# bmsMaster_conn.net
KiCad netlist of a schematic drawn in Altium Designer
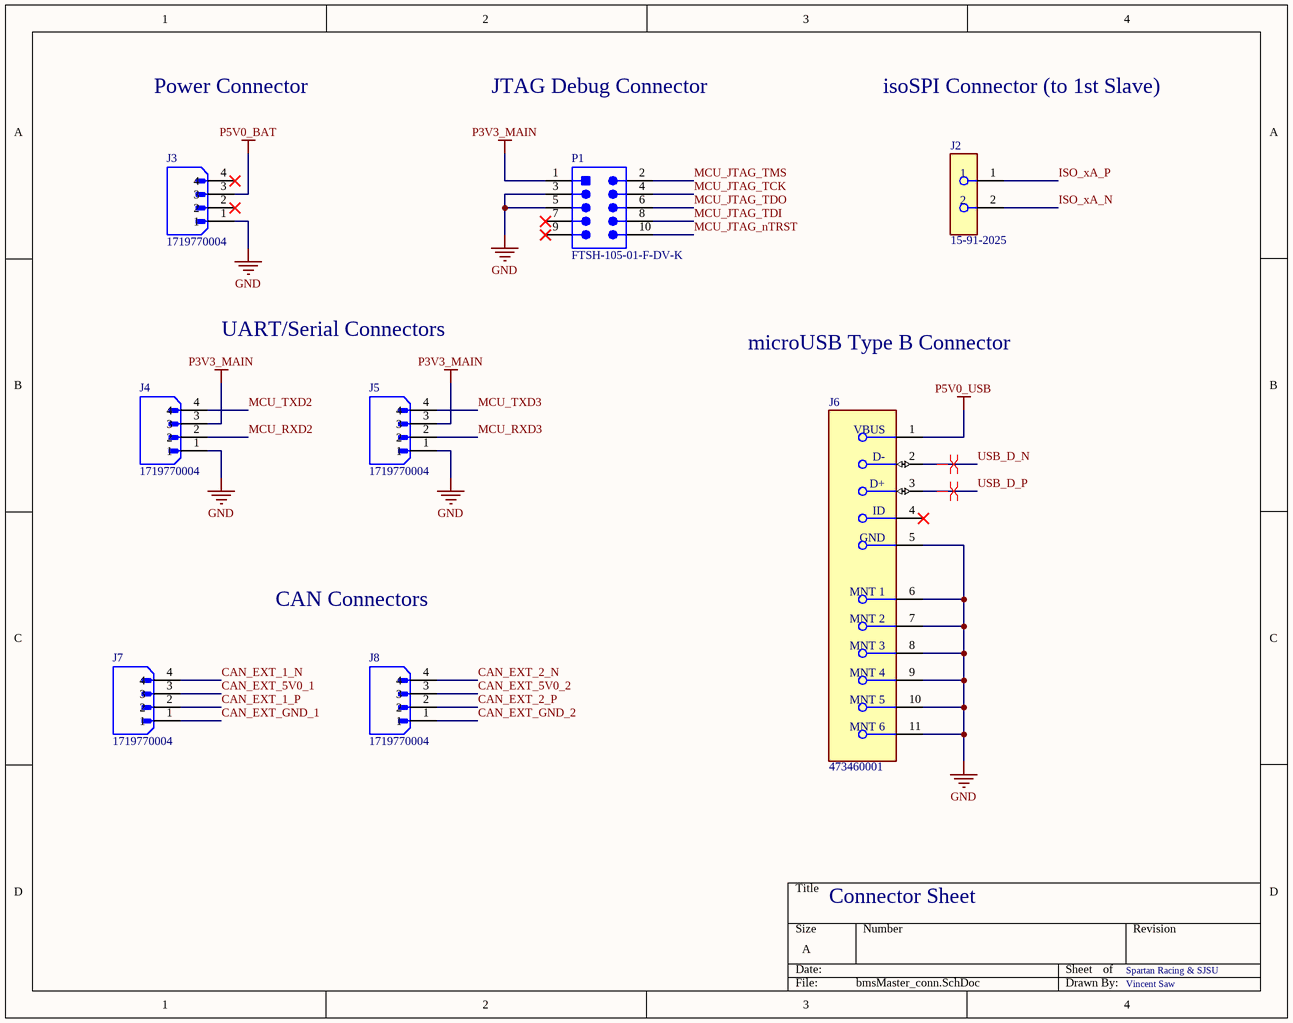
[diagram p0: bmsMaster_conn.SchDoc]

(export (version "E")
  (design (tool "Eeschema 10.0.6"))
  (components
    (comp (ref "J2")
      (value "15-91-2025")
      (footprint "FP-15-91-2025-MFG")
      (description "CONN HEADER SMD R/A 2POS 2.54MM")
      (libsource (lib "Altium Content Vault") (part "3ddab50f66188bb7952c54a1b76274c"))
    )
    (comp (ref "J3")
      (value "1719770004")
      (footprint "171977-0004:MOLEX_1719770004")
      (fields (field (name "MF") "{'manufacturer': u'Molex'}"))
      (libsource (lib "*") (part "1719770004"))
    )
    (comp (ref "J4")
      (value "1719770004")
      (footprint "171977-0004:MOLEX_1719770004")
      (fields (field (name "MF") "{'manufacturer': u'Molex'}"))
      (libsource (lib "*") (part "1719770004"))
    )
    (comp (ref "J5")
      (value "1719770004")
      (footprint "171977-0004:MOLEX_1719770004")
      (fields (field (name "MF") "{'manufacturer': u'Molex'}"))
      (libsource (lib "*") (part "1719770004"))
    )
    (comp (ref "J6")
      (value "473460001")
      (footprint "FP-473460001-MFG")
      (description "CONN RCPT USB2.0 MICRO B SMD R/A")
      (fields
        (field (name "OCTOPART") "https://octopart.com/47346-0001-molex-7164928")
        (field (name "MANUFACTURER") "Molex")
      )
      (libsource (lib "Altium Content Vault") (part "53ae1f1d9b557310b43ca686e5bb76a"))
    )
    (comp (ref "J7")
      (value "1719770004")
      (footprint "171977-0004:MOLEX_1719770004")
      (fields (field (name "MF") "{'manufacturer': u'Molex'}"))
      (libsource (lib "*") (part "1719770004"))
    )
    (comp (ref "J8")
      (value "1719770004")
      (footprint "171977-0004:MOLEX_1719770004")
      (fields (field (name "MF") "{'manufacturer': u'Molex'}"))
      (libsource (lib "*") (part "1719770004"))
    )
    (comp (ref "P1")
      (value "FTSH-105-01-F-DV-K")
      (footprint "SMTC-FTSH-105-01-L-DV-K_V")
      (description "Male Header, Pitch 1.27 mm, 2 x 5 Position, Height 6.12 mm, RoHS, Tube")
      (fields (field (name "MANUFACTURER") "Samtec"))
      (libsource (lib "Altium Content Vault") (part "CN-2P-M-R10"))
    )
  )
  (nets
    (net (code "1") (name "/CAN_EXT_1_N") (class "Default")
      (node (ref "J7") (pin "4") (pinfunction "4_4") (pintype "passive"))
    )
    (net (code "2") (name "/CAN_EXT_1_P") (class "Default")
      (node (ref "J7") (pin "2") (pinfunction "2_2") (pintype "passive"))
    )
    (net (code "3") (name "/CAN_EXT_2_N") (class "Default")
      (node (ref "J8") (pin "4") (pinfunction "4_4") (pintype "passive"))
    )
    (net (code "4") (name "/CAN_EXT_2_P") (class "Default")
      (node (ref "J8") (pin "2") (pinfunction "2_2") (pintype "passive"))
    )
    (net (code "5") (name "/CAN_EXT_5V0_1") (class "Default")
      (node (ref "J7") (pin "3") (pinfunction "3_3") (pintype "passive"))
    )
    (net (code "6") (name "/CAN_EXT_5V0_2") (class "Default")
      (node (ref "J8") (pin "3") (pinfunction "3_3") (pintype "passive"))
    )
    (net (code "7") (name "/CAN_EXT_GND_1") (class "Default")
      (node (ref "J7") (pin "1") (pinfunction "1_1") (pintype "passive"))
    )
    (net (code "8") (name "/CAN_EXT_GND_2") (class "Default")
      (node (ref "J8") (pin "1") (pinfunction "1_1") (pintype "passive"))
    )
    (net (code "9") (name "/ISO_xA_N") (class "Default")
      (node (ref "J2") (pin "2") (pinfunction "2_2") (pintype "passive"))
    )
    (net (code "10") (name "/ISO_xA_P") (class "Default")
      (node (ref "J2") (pin "1") (pinfunction "1_1") (pintype "passive"))
    )
    (net (code "11") (name "/MCU_JTAG_TCK") (class "Default")
      (node (ref "P1") (pin "4") (pinfunction "4_4") (pintype "passive"))
    )
    (net (code "12") (name "/MCU_JTAG_TDI") (class "Default")
      (node (ref "P1") (pin "8") (pinfunction "8_8") (pintype "passive"))
    )
    (net (code "13") (name "/MCU_JTAG_TDO") (class "Default")
      (node (ref "P1") (pin "6") (pinfunction "6_6") (pintype "passive"))
    )
    (net (code "14") (name "/MCU_JTAG_TMS") (class "Default")
      (node (ref "P1") (pin "2") (pinfunction "2_2") (pintype "passive"))
    )
    (net (code "15") (name "/MCU_JTAG_nTRST") (class "Default")
      (node (ref "P1") (pin "10") (pinfunction "10_10") (pintype "passive"))
    )
    (net (code "16") (name "/MCU_RXD2") (class "Default")
      (node (ref "J4") (pin "2") (pinfunction "2_2") (pintype "passive"))
    )
    (net (code "17") (name "/MCU_RXD3") (class "Default")
      (node (ref "J5") (pin "2") (pinfunction "2_2") (pintype "passive"))
    )
    (net (code "18") (name "/MCU_TXD2") (class "Default")
      (node (ref "J4") (pin "4") (pinfunction "4_4") (pintype "passive"))
    )
    (net (code "19") (name "/MCU_TXD3") (class "Default")
      (node (ref "J5") (pin "4") (pinfunction "4_4") (pintype "passive"))
    )
    (net (code "20") (name "/USB_D_N") (class "Default")
      (node (ref "J6") (pin "2") (pinfunction "D-_2") (pintype "bidirectional"))
    )
    (net (code "21") (name "/USB_D_P") (class "Default")
      (node (ref "J6") (pin "3") (pinfunction "D+_3") (pintype "bidirectional"))
    )
    (net (code "22") (name "GND") (class "Default")
      (node (ref "J3") (pin "1") (pinfunction "1_1") (pintype "passive"))
      (node (ref "J4") (pin "1") (pinfunction "1_1") (pintype "passive"))
      (node (ref "J5") (pin "1") (pinfunction "1_1") (pintype "passive"))
      (node (ref "J6") (pin "10") (pinfunction "MNT_5_10") (pintype "passive"))
      (node (ref "J6") (pin "11") (pinfunction "MNT_6_11") (pintype "passive"))
      (node (ref "J6") (pin "5") (pinfunction "GND_5") (pintype "power_in"))
      (node (ref "J6") (pin "6") (pinfunction "MNT_1_6") (pintype "passive"))
      (node (ref "J6") (pin "7") (pinfunction "MNT_2_7") (pintype "passive"))
      (node (ref "J6") (pin "8") (pinfunction "MNT_3_8") (pintype "passive"))
      (node (ref "J6") (pin "9") (pinfunction "MNT_4_9") (pintype "passive"))
      (node (ref "P1") (pin "3") (pinfunction "3_3") (pintype "passive"))
      (node (ref "P1") (pin "5") (pinfunction "5_5") (pintype "passive"))
    )
    (net (code "23") (name "P3V3_MAIN") (class "Default")
      (node (ref "J4") (pin "3") (pinfunction "3_3") (pintype "passive"))
      (node (ref "J5") (pin "3") (pinfunction "3_3") (pintype "passive"))
      (node (ref "P1") (pin "1") (pinfunction "1_1") (pintype "passive"))
    )
    (net (code "24") (name "P5V0_BAT") (class "Default")
      (node (ref "J3") (pin "3") (pinfunction "3_3") (pintype "passive"))
    )
    (net (code "25") (name "P5V0_USB") (class "Default")
      (node (ref "J6") (pin "1") (pinfunction "VBUS_1") (pintype "power_in"))
    )
    (net (code "26") (name "unconnected-(J3-Pad2)") (class "Default")
      (node (ref "J3") (pin "2") (pinfunction "2_2") (pintype "passive+no_connect"))
    )
    (net (code "27") (name "unconnected-(J3-Pad4)") (class "Default")
      (node (ref "J3") (pin "4") (pinfunction "4_4") (pintype "passive+no_connect"))
    )
    (net (code "28") (name "unconnected-(J6-ID-Pad4)") (class "Default")
      (node (ref "J6") (pin "4") (pinfunction "ID_4") (pintype "passive+no_connect"))
    )
    (net (code "29") (name "unconnected-(P1-Pad7)") (class "Default")
      (node (ref "P1") (pin "7") (pinfunction "7_7") (pintype "passive+no_connect"))
    )
    (net (code "30") (name "unconnected-(P1-Pad9)") (class "Default")
      (node (ref "P1") (pin "9") (pinfunction "9_9") (pintype "passive+no_connect"))
    )
  )
)
